# Jlink_V9.net
KiCad netlist of a schematic drawn in Altium Designer
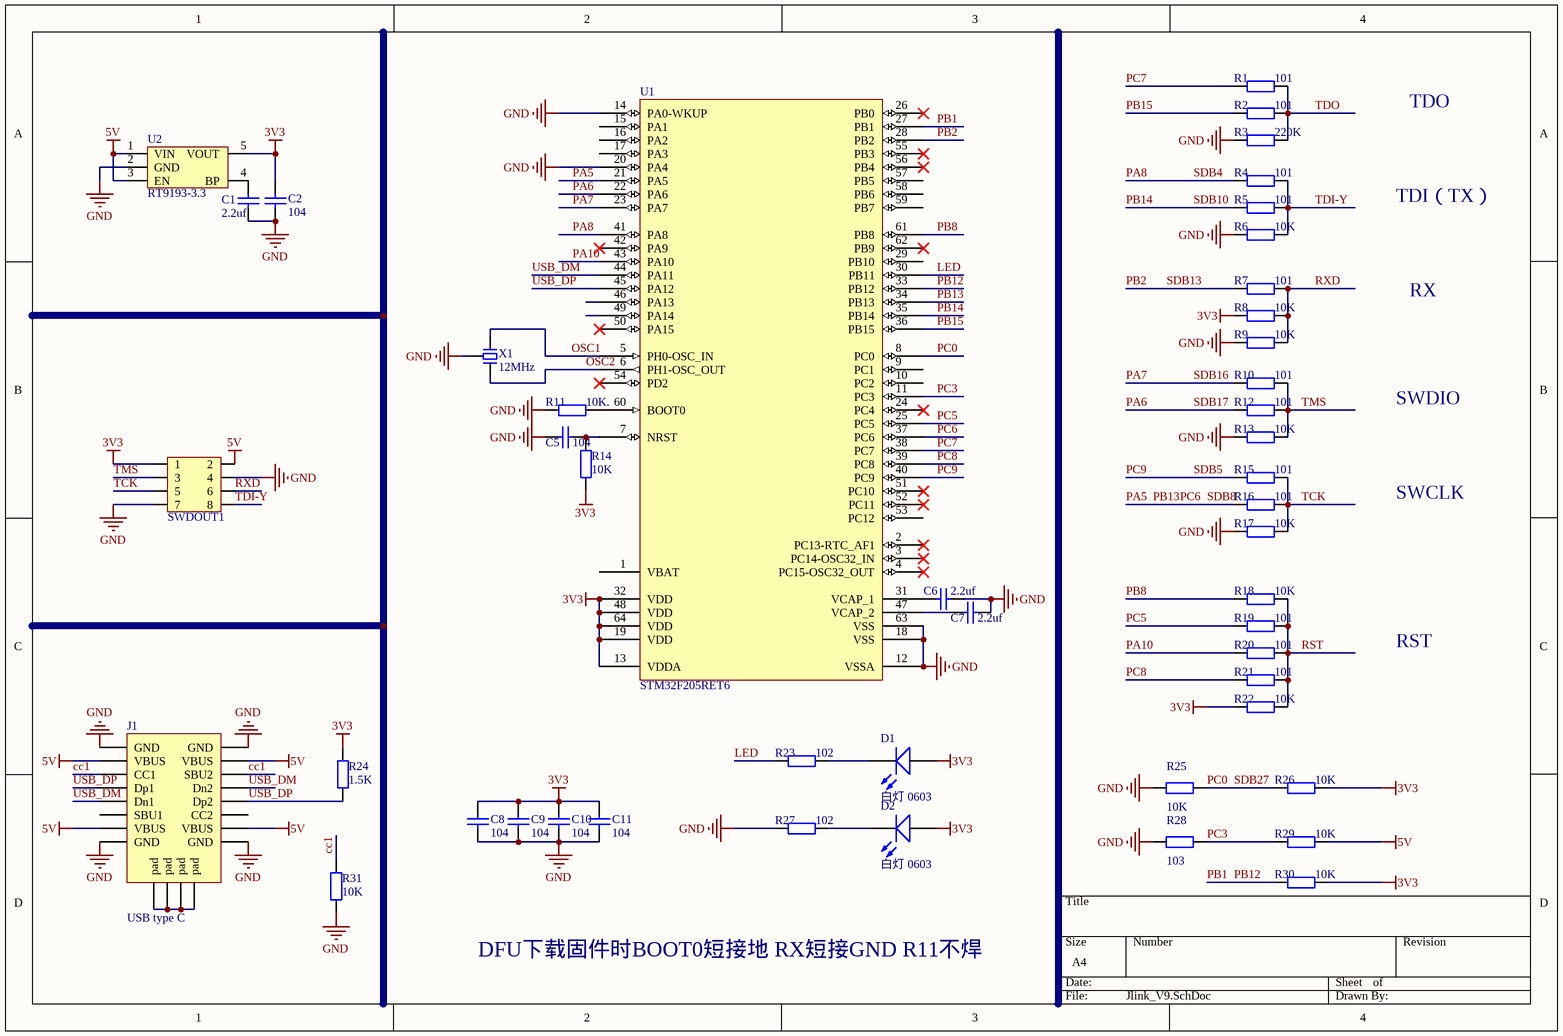
[diagram p0: Jlink_V9.SchDoc]

(export (version "E")
  (design (tool "Eeschema 10.0.6"))
  (components
    (comp (ref "C1")
      (value "2.2uf")
      (footprint "LC-0603_C")
      (description "Polarized Capacitor (Radial)")
      (fields (field (name "Comment") "2.2UF") (field (name "PUBLISHER") "Altium Limited"))
      (libsource (lib "Fantasy") (part "Cap"))
    )
    (comp (ref "C2")
      (value "104")
      (footprint "LC-0603_C")
      (description "Polarized Capacitor (Radial)")
      (fields (field (name "PUBLISHER") "Altium Limited"))
      (libsource (lib "Fantasy") (part "Cap"))
    )
    (comp (ref "C5")
      (value "104")
      (footprint "LC-0603_C")
      (description "Polarized Capacitor (Radial)")
      (fields (field (name "PUBLISHER") "Altium Limited"))
      (libsource (lib "Fantasy") (part "Cap"))
    )
    (comp (ref "C6")
      (value "2.2uf")
      (footprint "LC-0603_C")
      (description "Polarized Capacitor (Radial)")
      (fields (field (name "Comment") "2.2UF") (field (name "PUBLISHER") "Altium Limited"))
      (libsource (lib "Fantasy") (part "Cap"))
    )
    (comp (ref "C7")
      (value "2.2uf")
      (footprint "LC-0603_C")
      (description "Polarized Capacitor (Radial)")
      (fields (field (name "Comment") "2.2UF") (field (name "PUBLISHER") "Altium Limited"))
      (libsource (lib "Fantasy") (part "Cap"))
    )
    (comp (ref "C8")
      (value "104")
      (footprint "LC-0603_C")
      (description "Polarized Capacitor (Radial)")
      (fields (field (name "PUBLISHER") "Altium Limited"))
      (libsource (lib "Fantasy") (part "Cap"))
    )
    (comp (ref "C9")
      (value "104")
      (footprint "LC-0603_C")
      (description "Polarized Capacitor (Radial)")
      (fields (field (name "PUBLISHER") "Altium Limited"))
      (libsource (lib "Fantasy") (part "Cap"))
    )
    (comp (ref "C10")
      (value "104")
      (footprint "LC-0603_C")
      (description "Polarized Capacitor (Radial)")
      (fields (field (name "PUBLISHER") "Altium Limited"))
      (libsource (lib "Fantasy") (part "Cap"))
    )
    (comp (ref "C11")
      (value "104")
      (footprint "LC-0603_C")
      (description "Polarized Capacitor (Radial)")
      (fields (field (name "PUBLISHER") "Altium Limited"))
      (libsource (lib "Fantasy") (part "Cap"))
    )
    (comp (ref "D1")
      (value "白灯 0603")
      (footprint "0603_LED_S1")
      (description "发光二极管")
      (libsource (lib "Miscellaneous Devices LC") (part "0603 白灯"))
    )
    (comp (ref "D2")
      (value "白灯 0603")
      (footprint "0603_LED_S1")
      (description "发光二极管")
      (libsource (lib "Miscellaneous Devices LC") (part "0603 白灯"))
    )
    (comp (ref "J1")
      (value "USB type C")
      (footprint "USB Type-C-16Pin_A")
      (libsource (lib "XKZ") (part "USB_C"))
    )
    (comp (ref "R1")
      (value "101")
      (footprint "LC-0603_R")
      (description "Resistor Chip")
      (fields (field (name "Comment") "100R") (field (name "PUBLISHER") "Altium Limited"))
      (libsource (lib "Fantasy") (part "Resistor"))
    )
    (comp (ref "R2")
      (value "101")
      (footprint "LC-0603_R")
      (description "Resistor Chip")
      (fields (field (name "Comment") "100R") (field (name "PUBLISHER") "Altium Limited"))
      (libsource (lib "Fantasy") (part "Resistor"))
    )
    (comp (ref "R3")
      (value "220K")
      (footprint "LC-0603_R")
      (description "Resistor Chip")
      (fields (field (name "Comment") "NC") (field (name "PUBLISHER") "Altium Limited"))
      (libsource (lib "Fantasy") (part "Resistor"))
    )
    (comp (ref "R4")
      (value "101")
      (footprint "LC-0603_R")
      (description "Resistor Chip")
      (fields (field (name "Comment") "100R") (field (name "PUBLISHER") "Altium Limited"))
      (libsource (lib "Fantasy") (part "Resistor"))
    )
    (comp (ref "R5")
      (value "101")
      (footprint "LC-0603_R")
      (description "Resistor Chip")
      (fields (field (name "Comment") "100R") (field (name "PUBLISHER") "Altium Limited"))
      (libsource (lib "Fantasy") (part "Resistor"))
    )
    (comp (ref "R6")
      (value "10K")
      (footprint "LC-0603_R")
      (description "Resistor Chip")
      (fields (field (name "PUBLISHER") "Altium Limited"))
      (libsource (lib "Fantasy") (part "Resistor"))
    )
    (comp (ref "R7")
      (value "101")
      (footprint "LC-0603_R")
      (description "Resistor Chip")
      (fields (field (name "Comment") "100R") (field (name "PUBLISHER") "Altium Limited"))
      (libsource (lib "Fantasy") (part "Resistor"))
    )
    (comp (ref "R8")
      (value "10K")
      (footprint "LC-0603_R")
      (description "Resistor Chip")
      (fields (field (name "PUBLISHER") "Altium Limited"))
      (libsource (lib "Fantasy") (part "Resistor"))
    )
    (comp (ref "R9")
      (value "10K")
      (footprint "LC-0603_R")
      (description "Resistor Chip")
      (fields (field (name "PUBLISHER") "Altium Limited"))
      (libsource (lib "Fantasy") (part "Resistor"))
    )
    (comp (ref "R10")
      (value "101")
      (footprint "LC-0603_R")
      (description "Resistor Chip")
      (fields (field (name "Comment") "100R") (field (name "PUBLISHER") "Altium Limited"))
      (libsource (lib "Fantasy") (part "Resistor"))
    )
    (comp (ref "R11")
      (value "10K.")
      (footprint "LC-0603_R")
      (description "Resistor Chip")
      (fields (field (name "Comment") "10K") (field (name "PUBLISHER") "Altium Limited"))
      (libsource (lib "Fantasy") (part "Resistor"))
    )
    (comp (ref "R12")
      (value "101")
      (footprint "LC-0603_R")
      (description "Resistor Chip")
      (fields (field (name "Comment") "100R") (field (name "PUBLISHER") "Altium Limited"))
      (libsource (lib "Fantasy") (part "Resistor"))
    )
    (comp (ref "R13")
      (value "10K")
      (footprint "LC-0603_R")
      (description "Resistor Chip")
      (fields (field (name "PUBLISHER") "Altium Limited"))
      (libsource (lib "Fantasy") (part "Resistor"))
    )
    (comp (ref "R14")
      (value "10K")
      (footprint "LC-0603_R")
      (description "Resistor Chip")
      (fields (field (name "PUBLISHER") "Altium Limited"))
      (libsource (lib "") (part "Resistor_1"))
    )
    (comp (ref "R15")
      (value "101")
      (footprint "LC-0603_R")
      (description "Resistor Chip")
      (fields (field (name "Comment") "100R") (field (name "PUBLISHER") "Altium Limited"))
      (libsource (lib "Fantasy") (part "Resistor"))
    )
    (comp (ref "R16")
      (value "101")
      (footprint "LC-0603_R")
      (description "Resistor Chip")
      (fields (field (name "Comment") "100R") (field (name "PUBLISHER") "Altium Limited"))
      (libsource (lib "Fantasy") (part "Resistor"))
    )
    (comp (ref "R17")
      (value "10K")
      (footprint "LC-0603_R")
      (description "Resistor Chip")
      (fields (field (name "PUBLISHER") "Altium Limited"))
      (libsource (lib "Fantasy") (part "Resistor"))
    )
    (comp (ref "R18")
      (value "10K")
      (footprint "LC-0603_R")
      (description "Resistor Chip")
      (fields (field (name "PUBLISHER") "Altium Limited"))
      (libsource (lib "Fantasy") (part "Resistor"))
    )
    (comp (ref "R19")
      (value "101")
      (footprint "LC-0603_R")
      (description "Resistor Chip")
      (fields (field (name "Comment") "100R") (field (name "PUBLISHER") "Altium Limited"))
      (libsource (lib "Fantasy") (part "Resistor"))
    )
    (comp (ref "R20")
      (value "101")
      (footprint "LC-0603_R")
      (description "Resistor Chip")
      (fields (field (name "Comment") "100R") (field (name "PUBLISHER") "Altium Limited"))
      (libsource (lib "Fantasy") (part "Resistor"))
    )
    (comp (ref "R21")
      (value "101")
      (footprint "LC-0603_R")
      (description "Resistor Chip")
      (fields (field (name "Comment") "10K") (field (name "PUBLISHER") "Altium Limited"))
      (libsource (lib "Fantasy") (part "Resistor"))
    )
    (comp (ref "R22")
      (value "10K")
      (footprint "LC-0603_R")
      (description "Resistor Chip")
      (fields (field (name "PUBLISHER") "Altium Limited"))
      (libsource (lib "Fantasy") (part "Resistor"))
    )
    (comp (ref "R23")
      (value "102")
      (footprint "LC-0603_R")
      (description "Resistor Chip")
      (fields (field (name "Comment") "1K") (field (name "PUBLISHER") "Altium Limited"))
      (libsource (lib "Fantasy") (part "Resistor"))
    )
    (comp (ref "R24")
      (value "1.5K")
      (footprint "LC-0603_R")
      (description "Resistor")
      (fields (field (name "PUBLISHER") "Altium Limited"))
      (libsource (lib "XKZ") (part "Res2"))
    )
    (comp (ref "R25")
      (value "10K")
      (footprint "LC-0603_R")
      (description "Resistor Chip")
      (fields (field (name "PUBLISHER") "Altium Limited"))
      (libsource (lib "Fantasy") (part "Resistor"))
    )
    (comp (ref "R26")
      (value "10K")
      (footprint "LC-0603_R")
      (description "Resistor Chip")
      (fields (field (name "PUBLISHER") "Altium Limited"))
      (libsource (lib "Fantasy") (part "Resistor"))
    )
    (comp (ref "R27")
      (value "102")
      (footprint "LC-0603_R")
      (description "Resistor Chip")
      (fields (field (name "Comment") "1K") (field (name "PUBLISHER") "Altium Limited"))
      (libsource (lib "Fantasy") (part "Resistor"))
    )
    (comp (ref "R28")
      (value "103")
      (footprint "LC-0603_R")
      (description "Resistor Chip")
      (fields (field (name "Comment") "10K") (field (name "PUBLISHER") "Altium Limited"))
      (libsource (lib "Fantasy") (part "Resistor"))
    )
    (comp (ref "R29")
      (value "10K")
      (footprint "LC-0603_R")
      (description "Resistor Chip")
      (fields (field (name "PUBLISHER") "Altium Limited"))
      (libsource (lib "Fantasy") (part "Resistor"))
    )
    (comp (ref "R30")
      (value "10K")
      (footprint "LC-0603_R")
      (description "Resistor Chip")
      (fields (field (name "PUBLISHER") "Altium Limited"))
      (libsource (lib "Fantasy") (part "Resistor"))
    )
    (comp (ref "R31")
      (value "10K")
      (footprint "LC-0603_R")
      (description "Resistor")
      (fields (field (name "PUBLISHER") "Altium Limited"))
      (libsource (lib "XKZ") (part "Res2"))
    )
    (comp (ref "SWDOUT1")
      (value "HDR2x6_2.54")
      (footprint "PCB_ConnectorHDR:HDR2X4_2.54_180H")
      (description "Header")
      (libsource (lib "SCH_ConnectorHDR") (part "HDR2x4_2.54"))
    )
    (comp (ref "U1")
      (value "STM32F205RET6")
      (footprint "LQFP64 10x10_N")
      (description "Microcontroller   ST")
      (libsource (lib "Fantasy") (part "STM32F205RET6"))
    )
    (comp (ref "U2")
      (value "RT9193-3.3")
      (footprint "SOT23-5N")
      (description "3.3V超低压差LDO")
      (libsource (lib "Fantasy") (part "RT9193-33"))
    )
    (comp (ref "X1")
      (value "12MHz")
      (footprint "3脚晶振")
      (description "3脚无源晶振")
      (fields (field (name "版权归属") "源创客"))
      (libsource (lib "ATKF405 V1.1") (part "XTAL-3P"))
    )
  )
  (nets
    (net (code "1") (name "/LED") (class "Default")
      (node (ref "R23") (pin "1") (pinfunction "1_1") (pintype "passive"))
      (node (ref "U1") (pin "30") (pinfunction "PB11_30") (pintype "bidirectional"))
    )
    (net (code "2") (name "/OSC1") (class "Default")
      (node (ref "U1") (pin "5") (pinfunction "PH0-OSC_IN_5") (pintype "input"))
      (node (ref "X1") (pin "1") (pinfunction "1_1") (pintype "passive"))
    )
    (net (code "3") (name "/OSC2") (class "Default")
      (node (ref "U1") (pin "6") (pinfunction "PH1-OSC_OUT_6") (pintype "output"))
      (node (ref "X1") (pin "2") (pinfunction "2_2") (pintype "passive"))
    )
    (net (code "4") (name "/PA5") (class "Default")
      (node (ref "R16") (pin "1") (pinfunction "1_1") (pintype "passive"))
      (node (ref "U1") (pin "21") (pinfunction "PA5_21") (pintype "bidirectional"))
      (node (ref "U1") (pin "34") (pinfunction "PB13_34") (pintype "bidirectional"))
      (node (ref "U1") (pin "37") (pinfunction "PC6_37") (pintype "bidirectional"))
    )
    (net (code "5") (name "/PA6") (class "Default")
      (node (ref "R12") (pin "1") (pinfunction "1_1") (pintype "passive"))
      (node (ref "U1") (pin "22") (pinfunction "PA6_22") (pintype "bidirectional"))
    )
    (net (code "6") (name "/PA7") (class "Default")
      (node (ref "R10") (pin "1") (pinfunction "1_1") (pintype "passive"))
      (node (ref "U1") (pin "23") (pinfunction "PA7_23") (pintype "bidirectional"))
    )
    (net (code "7") (name "/PA8") (class "Default")
      (node (ref "R4") (pin "1") (pinfunction "1_1") (pintype "passive"))
      (node (ref "U1") (pin "41") (pinfunction "PA8_41") (pintype "bidirectional"))
    )
    (net (code "8") (name "/PA10") (class "Default")
      (node (ref "R20") (pin "1") (pinfunction "1_1") (pintype "passive"))
      (node (ref "U1") (pin "43") (pinfunction "PA10_43") (pintype "bidirectional"))
    )
    (net (code "9") (name "/PB1") (class "Default")
      (node (ref "R30") (pin "1") (pinfunction "1_1") (pintype "passive"))
      (node (ref "U1") (pin "27") (pinfunction "PB1_27") (pintype "bidirectional"))
      (node (ref "U1") (pin "33") (pinfunction "PB12_33") (pintype "bidirectional"))
    )
    (net (code "10") (name "/PB2") (class "Default")
      (node (ref "R7") (pin "1") (pinfunction "1_1") (pintype "passive"))
      (node (ref "U1") (pin "28") (pinfunction "PB2_28") (pintype "bidirectional"))
    )
    (net (code "11") (name "/PB8") (class "Default")
      (node (ref "R18") (pin "1") (pinfunction "1_1") (pintype "passive"))
      (node (ref "U1") (pin "61") (pinfunction "PB8_61") (pintype "bidirectional"))
    )
    (net (code "12") (name "/PB14") (class "Default")
      (node (ref "R5") (pin "1") (pinfunction "1_1") (pintype "passive"))
      (node (ref "U1") (pin "35") (pinfunction "PB14_35") (pintype "bidirectional"))
    )
    (net (code "13") (name "/PB15") (class "Default")
      (node (ref "R2") (pin "1") (pinfunction "1_1") (pintype "passive"))
      (node (ref "U1") (pin "36") (pinfunction "PB15_36") (pintype "bidirectional"))
    )
    (net (code "14") (name "/PC0") (class "Default")
      (node (ref "R25") (pin "2") (pinfunction "2_2") (pintype "passive"))
      (node (ref "R26") (pin "1") (pinfunction "1_1") (pintype "passive"))
      (node (ref "U1") (pin "8") (pinfunction "PC0_8") (pintype "bidirectional"))
    )
    (net (code "15") (name "/PC3") (class "Default")
      (node (ref "R28") (pin "2") (pinfunction "2_2") (pintype "passive"))
      (node (ref "R29") (pin "1") (pinfunction "1_1") (pintype "passive"))
      (node (ref "U1") (pin "11") (pinfunction "PC3_11") (pintype "bidirectional"))
    )
    (net (code "16") (name "/PC5") (class "Default")
      (node (ref "R19") (pin "1") (pinfunction "1_1") (pintype "passive"))
      (node (ref "U1") (pin "25") (pinfunction "PC5_25") (pintype "bidirectional"))
    )
    (net (code "17") (name "/PC7") (class "Default")
      (node (ref "R1") (pin "1") (pinfunction "1_1") (pintype "passive"))
      (node (ref "U1") (pin "38") (pinfunction "PC7_38") (pintype "bidirectional"))
    )
    (net (code "18") (name "/PC8") (class "Default")
      (node (ref "R21") (pin "1") (pinfunction "1_1") (pintype "passive"))
      (node (ref "U1") (pin "39") (pinfunction "PC8_39") (pintype "bidirectional"))
    )
    (net (code "19") (name "/PC9") (class "Default")
      (node (ref "R15") (pin "1") (pinfunction "1_1") (pintype "passive"))
      (node (ref "U1") (pin "40") (pinfunction "PC9_40") (pintype "bidirectional"))
    )
    (net (code "20") (name "/RST") (class "Default")
      (node (ref "R18") (pin "2") (pinfunction "2_2") (pintype "passive"))
      (node (ref "R19") (pin "2") (pinfunction "2_2") (pintype "passive"))
      (node (ref "R20") (pin "2") (pinfunction "2_2") (pintype "passive"))
      (node (ref "R21") (pin "2") (pinfunction "2_2") (pintype "passive"))
      (node (ref "R22") (pin "2") (pinfunction "2_2") (pintype "passive"))
    )
    (net (code "21") (name "/RXD") (class "Default")
      (node (ref "R7") (pin "2") (pinfunction "2_2") (pintype "passive"))
      (node (ref "R8") (pin "2") (pinfunction "2_2") (pintype "passive"))
      (node (ref "R9") (pin "2") (pinfunction "2_2") (pintype "passive"))
      (node (ref "SWDOUT1") (pin "6") (pinfunction "6_6") (pintype "passive"))
    )
    (net (code "22") (name "/TCK") (class "Default")
      (node (ref "R15") (pin "2") (pinfunction "2_2") (pintype "passive"))
      (node (ref "R16") (pin "2") (pinfunction "2_2") (pintype "passive"))
      (node (ref "R17") (pin "2") (pinfunction "2_2") (pintype "passive"))
      (node (ref "SWDOUT1") (pin "5") (pinfunction "5_5") (pintype "passive"))
    )
    (net (code "23") (name "/TDI-Y") (class "Default")
      (node (ref "R4") (pin "2") (pinfunction "2_2") (pintype "passive"))
      (node (ref "R5") (pin "2") (pinfunction "2_2") (pintype "passive"))
      (node (ref "R6") (pin "2") (pinfunction "2_2") (pintype "passive"))
      (node (ref "SWDOUT1") (pin "8") (pinfunction "8_8") (pintype "passive"))
    )
    (net (code "24") (name "/TDO") (class "Default")
      (node (ref "R1") (pin "2") (pinfunction "2_2") (pintype "passive"))
      (node (ref "R2") (pin "2") (pinfunction "2_2") (pintype "passive"))
      (node (ref "R3") (pin "2") (pinfunction "2_2") (pintype "passive"))
    )
    (net (code "25") (name "/TMS") (class "Default")
      (node (ref "R10") (pin "2") (pinfunction "2_2") (pintype "passive"))
      (node (ref "R12") (pin "2") (pinfunction "2_2") (pintype "passive"))
      (node (ref "R13") (pin "2") (pinfunction "2_2") (pintype "passive"))
      (node (ref "SWDOUT1") (pin "3") (pinfunction "3_3") (pintype "passive"))
    )
    (net (code "26") (name "/USB_DM") (class "Default")
      (node (ref "J1") (pin "A7") (pinfunction "Dn1_A7") (pintype "passive"))
      (node (ref "J1") (pin "B7") (pinfunction "Dn2_B7") (pintype "passive"))
      (node (ref "U1") (pin "44") (pinfunction "PA11_44") (pintype "bidirectional"))
    )
    (net (code "27") (name "/USB_DP") (class "Default")
      (node (ref "J1") (pin "A6") (pinfunction "Dp1_A6") (pintype "passive"))
      (node (ref "J1") (pin "B6") (pinfunction "Dp2_B6") (pintype "passive"))
      (node (ref "R24") (pin "2") (pinfunction "2_2") (pintype "passive"))
      (node (ref "U1") (pin "45") (pinfunction "PA12_45") (pintype "bidirectional"))
    )
    (net (code "28") (name "/cc1") (class "Default")
      (node (ref "J1") (pin "A5") (pinfunction "CC1_A5") (pintype "passive"))
      (node (ref "J1") (pin "B8") (pinfunction "SBU2_B8") (pintype "passive"))
      (node (ref "R31") (pin "1") (pinfunction "1_1") (pintype "passive"))
    )
    (net (code "29") (name "3V3") (class "Default")
      (node (ref "C10") (pin "2") (pinfunction "2_2") (pintype "passive"))
      (node (ref "C11") (pin "2") (pinfunction "2_2") (pintype "passive"))
      (node (ref "C2") (pin "2") (pinfunction "2_2") (pintype "passive"))
      (node (ref "C8") (pin "2") (pinfunction "2_2") (pintype "passive"))
      (node (ref "C9") (pin "2") (pinfunction "2_2") (pintype "passive"))
      (node (ref "D1") (pin "A") (pinfunction "A_A") (pintype "passive"))
      (node (ref "D2") (pin "A") (pinfunction "A_A") (pintype "passive"))
      (node (ref "R14") (pin "1") (pinfunction "1_1") (pintype "passive"))
      (node (ref "R22") (pin "1") (pinfunction "1_1") (pintype "passive"))
      (node (ref "R24") (pin "1") (pinfunction "1_1") (pintype "passive"))
      (node (ref "R26") (pin "2") (pinfunction "2_2") (pintype "passive"))
      (node (ref "R30") (pin "2") (pinfunction "2_2") (pintype "passive"))
      (node (ref "R8") (pin "1") (pinfunction "1_1") (pintype "passive"))
      (node (ref "SWDOUT1") (pin "1") (pinfunction "1_1") (pintype "passive"))
      (node (ref "U1") (pin "13") (pinfunction "VDDA_13") (pintype "power_in"))
      (node (ref "U1") (pin "19") (pinfunction "VDD_19") (pintype "power_in"))
      (node (ref "U1") (pin "32") (pinfunction "VDD_32") (pintype "power_in"))
      (node (ref "U1") (pin "48") (pinfunction "VDD_48") (pintype "power_in"))
      (node (ref "U1") (pin "64") (pinfunction "VDD_64") (pintype "power_in"))
      (node (ref "U2") (pin "5") (pinfunction "VOUT_5") (pintype "passive"))
    )
    (net (code "30") (name "5V") (class "Default")
      (node (ref "J1") (pin "A4") (pinfunction "VBUS_A4") (pintype "passive"))
      (node (ref "J1") (pin "A9") (pinfunction "VBUS_A9") (pintype "passive"))
      (node (ref "J1") (pin "B4") (pinfunction "VBUS_B4") (pintype "passive"))
      (node (ref "J1") (pin "B9") (pinfunction "VBUS_B9") (pintype "passive"))
      (node (ref "R29") (pin "2") (pinfunction "2_2") (pintype "passive"))
      (node (ref "SWDOUT1") (pin "2") (pinfunction "2_2") (pintype "passive"))
      (node (ref "U2") (pin "1") (pinfunction "VIN_1") (pintype "passive"))
      (node (ref "U2") (pin "3") (pinfunction "EN_3") (pintype "passive"))
    )
    (net (code "31") (name "GND") (class "Default")
      (node (ref "C1") (pin "1") (pinfunction "1_1") (pintype "passive"))
      (node (ref "C10") (pin "1") (pinfunction "1_1") (pintype "passive"))
      (node (ref "C11") (pin "1") (pinfunction "1_1") (pintype "passive"))
      (node (ref "C2") (pin "1") (pinfunction "1_1") (pintype "passive"))
      (node (ref "C5") (pin "2") (pinfunction "2_2") (pintype "passive"))
      (node (ref "C6") (pin "1") (pinfunction "1_1") (pintype "passive"))
      (node (ref "C7") (pin "1") (pinfunction "1_1") (pintype "passive"))
      (node (ref "C8") (pin "1") (pinfunction "1_1") (pintype "passive"))
      (node (ref "C9") (pin "1") (pinfunction "1_1") (pintype "passive"))
      (node (ref "J1") (pin "A1") (pinfunction "GND_A1") (pintype "passive"))
      (node (ref "J1") (pin "A12") (pinfunction "GND_A12") (pintype "passive"))
      (node (ref "J1") (pin "B1") (pinfunction "GND_B1") (pintype "passive"))
      (node (ref "J1") (pin "B12") (pinfunction "GND_B12") (pintype "passive"))
      (node (ref "R11") (pin "1") (pinfunction "1_1") (pintype "passive"))
      (node (ref "R13") (pin "1") (pinfunction "1_1") (pintype "passive"))
      (node (ref "R17") (pin "1") (pinfunction "1_1") (pintype "passive"))
      (node (ref "R25") (pin "1") (pinfunction "1_1") (pintype "passive"))
      (node (ref "R27") (pin "1") (pinfunction "1_1") (pintype "passive"))
      (node (ref "R28") (pin "1") (pinfunction "1_1") (pintype "passive"))
      (node (ref "R3") (pin "1") (pinfunction "1_1") (pintype "passive"))
      (node (ref "R31") (pin "2") (pinfunction "2_2") (pintype "passive"))
      (node (ref "R6") (pin "1") (pinfunction "1_1") (pintype "passive"))
      (node (ref "R9") (pin "1") (pinfunction "1_1") (pintype "passive"))
      (node (ref "SWDOUT1") (pin "4") (pinfunction "4_4") (pintype "passive"))
      (node (ref "SWDOUT1") (pin "7") (pinfunction "7_7") (pintype "passive"))
      (node (ref "U1") (pin "12") (pinfunction "VSSA_12") (pintype "power_in"))
      (node (ref "U1") (pin "14") (pinfunction "PA0-WKUP_14") (pintype "bidirectional"))
      (node (ref "U1") (pin "18") (pinfunction "VSS_18") (pintype "power_in"))
      (node (ref "U1") (pin "20") (pinfunction "PA4_20") (pintype "bidirectional"))
      (node (ref "U1") (pin "63") (pinfunction "VSS_63") (pintype "power_in"))
      (node (ref "U2") (pin "2") (pinfunction "GND_2") (pintype "passive"))
      (node (ref "X1") (pin "3") (pinfunction "3_3") (pintype "passive"))
    )
    (net (code "32") (name "Net-(D1-PadK)") (class "Default")
      (node (ref "D1") (pin "K") (pinfunction "K_K") (pintype "passive"))
      (node (ref "R23") (pin "2") (pinfunction "2_2") (pintype "passive"))
    )
    (net (code "33") (name "Net-(D2-PadK)") (class "Default")
      (node (ref "D2") (pin "K") (pinfunction "K_K") (pintype "passive"))
      (node (ref "R27") (pin "2") (pinfunction "2_2") (pintype "passive"))
    )
    (net (code "34") (name "Net-(J1-pad)") (class "Default")
      (node (ref "J1") (pin "0") (pinfunction "pad_0") (pintype "passive"))
    )
    (net (code "35") (name "Net-(U1-BOOT0)") (class "Default")
      (node (ref "R11") (pin "2") (pinfunction "2_2") (pintype "passive"))
      (node (ref "U1") (pin "60") (pinfunction "BOOT0_60") (pintype "input"))
    )
    (net (code "36") (name "Net-(U1-NRST)") (class "Default")
      (node (ref "C5") (pin "1") (pinfunction "1_1") (pintype "passive"))
      (node (ref "R14") (pin "2") (pinfunction "2_2") (pintype "passive"))
      (node (ref "U1") (pin "7") (pinfunction "NRST_7") (pintype "bidirectional"))
    )
    (net (code "37") (name "Net-(U1-VCAP_1)") (class "Default")
      (node (ref "C6") (pin "2") (pinfunction "2_2") (pintype "passive"))
      (node (ref "U1") (pin "31") (pinfunction "VCAP_1_31") (pintype "power_in"))
    )
    (net (code "38") (name "Net-(U1-VCAP_2)") (class "Default")
      (node (ref "C7") (pin "2") (pinfunction "2_2") (pintype "passive"))
      (node (ref "U1") (pin "47") (pinfunction "VCAP_2_47") (pintype "power_in"))
    )
    (net (code "39") (name "Net-(U2-BP)") (class "Default")
      (node (ref "C1") (pin "2") (pinfunction "2_2") (pintype "passive"))
      (node (ref "U2") (pin "4") (pinfunction "BP_4") (pintype "passive"))
    )
    (net (code "40") (name "unconnected-(J1-CC2-PadB5)") (class "Default")
      (node (ref "J1") (pin "B5") (pinfunction "CC2_B5") (pintype "passive"))
    )
    (net (code "41") (name "unconnected-(J1-SBU1-PadA8)") (class "Default")
      (node (ref "J1") (pin "A8") (pinfunction "SBU1_A8") (pintype "passive"))
    )
    (net (code "42") (name "unconnected-(U1-PA1-Pad15)") (class "Default")
      (node (ref "U1") (pin "15") (pinfunction "PA1_15") (pintype "bidirectional"))
    )
    (net (code "43") (name "unconnected-(U1-PA2-Pad16)") (class "Default")
      (node (ref "U1") (pin "16") (pinfunction "PA2_16") (pintype "bidirectional"))
    )
    (net (code "44") (name "unconnected-(U1-PA3-Pad17)") (class "Default")
      (node (ref "U1") (pin "17") (pinfunction "PA3_17") (pintype "bidirectional"))
    )
    (net (code "45") (name "unconnected-(U1-PA9-Pad42)") (class "Default")
      (node (ref "U1") (pin "42") (pinfunction "PA9_42") (pintype "bidirectional+no_connect"))
    )
    (net (code "46") (name "unconnected-(U1-PA13-Pad46)") (class "Default")
      (node (ref "U1") (pin "46") (pinfunction "PA13_46") (pintype "bidirectional"))
    )
    (net (code "47") (name "unconnected-(U1-PA14-Pad49)") (class "Default")
      (node (ref "U1") (pin "49") (pinfunction "PA14_49") (pintype "bidirectional"))
    )
    (net (code "48") (name "unconnected-(U1-PA15-Pad50)") (class "Default")
      (node (ref "U1") (pin "50") (pinfunction "PA15_50") (pintype "bidirectional+no_connect"))
    )
    (net (code "49") (name "unconnected-(U1-PB0-Pad26)") (class "Default")
      (node (ref "U1") (pin "26") (pinfunction "PB0_26") (pintype "bidirectional+no_connect"))
    )
    (net (code "50") (name "unconnected-(U1-PB3-Pad55)") (class "Default")
      (node (ref "U1") (pin "55") (pinfunction "PB3_55") (pintype "bidirectional+no_connect"))
    )
    (net (code "51") (name "unconnected-(U1-PB4-Pad56)") (class "Default")
      (node (ref "U1") (pin "56") (pinfunction "PB4_56") (pintype "bidirectional+no_connect"))
    )
    (net (code "52") (name "unconnected-(U1-PB5-Pad57)") (class "Default")
      (node (ref "U1") (pin "57") (pinfunction "PB5_57") (pintype "bidirectional"))
    )
    (net (code "53") (name "unconnected-(U1-PB6-Pad58)") (class "Default")
      (node (ref "U1") (pin "58") (pinfunction "PB6_58") (pintype "bidirectional"))
    )
    (net (code "54") (name "unconnected-(U1-PB7-Pad59)") (class "Default")
      (node (ref "U1") (pin "59") (pinfunction "PB7_59") (pintype "bidirectional"))
    )
    (net (code "55") (name "unconnected-(U1-PB9-Pad62)") (class "Default")
      (node (ref "U1") (pin "62") (pinfunction "PB9_62") (pintype "bidirectional+no_connect"))
    )
    (net (code "56") (name "unconnected-(U1-PB10-Pad29)") (class "Default")
      (node (ref "U1") (pin "29") (pinfunction "PB10_29") (pintype "bidirectional"))
    )
    (net (code "57") (name "unconnected-(U1-PC1-Pad9)") (class "Default")
      (node (ref "U1") (pin "9") (pinfunction "PC1_9") (pintype "bidirectional"))
    )
    (net (code "58") (name "unconnected-(U1-PC2-Pad10)") (class "Default")
      (node (ref "U1") (pin "10") (pinfunction "PC2_10") (pintype "bidirectional"))
    )
    (net (code "59") (name "unconnected-(U1-PC4-Pad24)") (class "Default")
      (node (ref "U1") (pin "24") (pinfunction "PC4_24") (pintype "bidirectional+no_connect"))
    )
    (net (code "60") (name "unconnected-(U1-PC10-Pad51)") (class "Default")
      (node (ref "U1") (pin "51") (pinfunction "PC10_51") (pintype "bidirectional+no_connect"))
    )
    (net (code "61") (name "unconnected-(U1-PC11-Pad52)") (class "Default")
      (node (ref "U1") (pin "52") (pinfunction "PC11_52") (pintype "bidirectional+no_connect"))
    )
    (net (code "62") (name "unconnected-(U1-PC12-Pad53)") (class "Default")
      (node (ref "U1") (pin "53") (pinfunction "PC12_53") (pintype "bidirectional"))
    )
    (net (code "63") (name "unconnected-(U1-PC13-RTC_AF1-Pad2)") (class "Default")
      (node (ref "U1") (pin "2") (pinfunction "PC13-RTC_AF1_2") (pintype "bidirectional+no_connect"))
    )
    (net (code "64") (name "unconnected-(U1-PC14-OSC32_IN-Pad3)") (class "Default")
      (node (ref "U1") (pin "3") (pinfunction "PC14-OSC32_IN_3") (pintype "bidirectional+no_connect"))
    )
    (net (code "65") (name "unconnected-(U1-PC15-OSC32_OUT-Pad4)") (class "Default")
      (node (ref "U1") (pin "4") (pinfunction "PC15-OSC32_OUT_4") (pintype "bidirectional+no_connect"))
    )
    (net (code "66") (name "unconnected-(U1-PD2-Pad54)") (class "Default")
      (node (ref "U1") (pin "54") (pinfunction "PD2_54") (pintype "bidirectional+no_connect"))
    )
    (net (code "67") (name "unconnected-(U1-VBAT-Pad1)") (class "Default")
      (node (ref "U1") (pin "1") (pinfunction "VBAT_1") (pintype "power_in"))
    )
  )
)
